# JLINK-OB.net
KiCad netlist of a schematic drawn in EasyEDA Pro
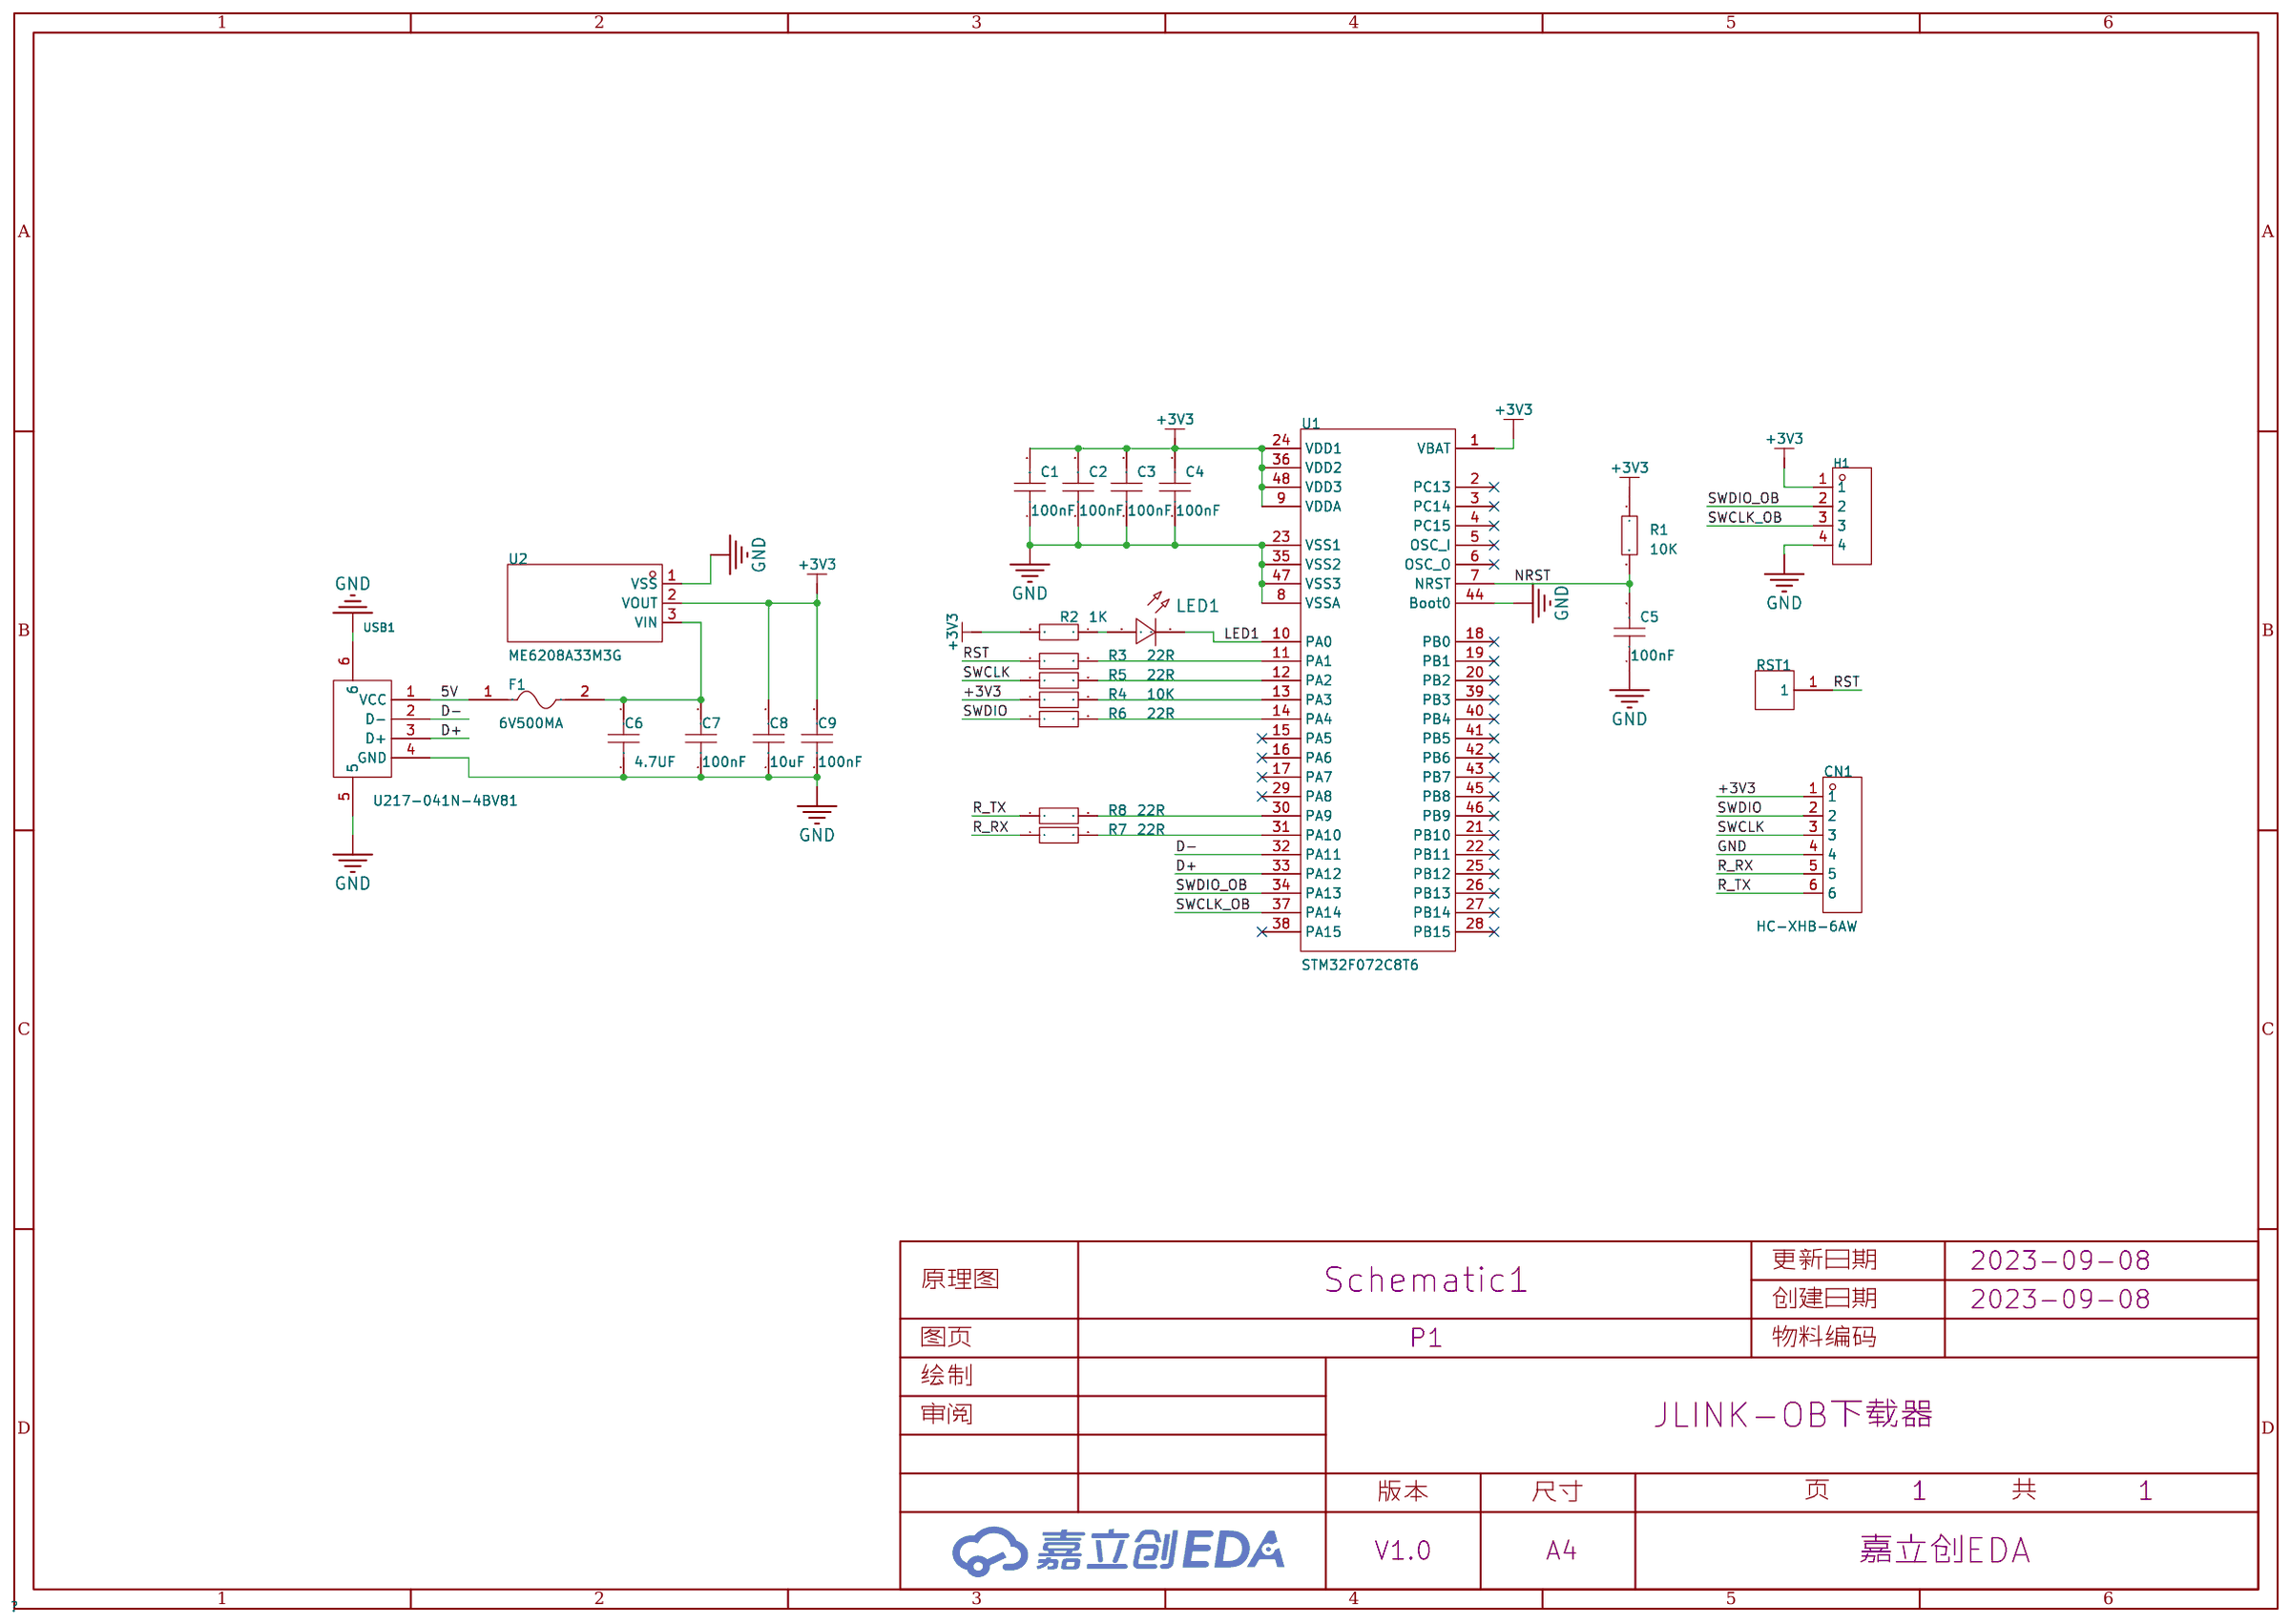
[diagram p0: schematic sheet]

(export (version "E")
  (design (tool "Eeschema 10.0.6"))
  (components
    (comp (ref "C1")
      (value "100nF")
      (footprint "easyedapro:C0603")
      (libsource (lib "easyedapro") (part "CapAcitance"))
    )
    (comp (ref "C2")
      (value "100nF")
      (footprint "easyedapro:C0603")
      (libsource (lib "easyedapro") (part "CapAcitance"))
    )
    (comp (ref "C3")
      (value "100nF")
      (footprint "easyedapro:C0603")
      (libsource (lib "easyedapro") (part "CapAcitance"))
    )
    (comp (ref "C4")
      (value "100nF")
      (footprint "easyedapro:C0603")
      (libsource (lib "easyedapro") (part "CapAcitance"))
    )
    (comp (ref "C5")
      (value "100nF")
      (footprint "easyedapro:C0603")
      (libsource (lib "easyedapro") (part "CapAcitance"))
    )
    (comp (ref "C6")
      (value "4.7UF")
      (footprint "easyedapro:C0603")
      (libsource (lib "easyedapro") (part "CapAcitance"))
    )
    (comp (ref "C7")
      (value "100nF")
      (footprint "easyedapro:C0603")
      (libsource (lib "easyedapro") (part "CapAcitance"))
    )
    (comp (ref "C8")
      (value "10uF")
      (footprint "easyedapro:C0603")
      (libsource (lib "easyedapro") (part "CapAcitance"))
    )
    (comp (ref "C9")
      (value "100nF")
      (footprint "easyedapro:C0603")
      (libsource (lib "easyedapro") (part "CapAcitance"))
    )
    (comp (ref "CN1")
      (value "HC-XHB-6AW")
      (footprint "easyedapro:CONN-TH_6P-P2.50_HCTL_HC-XHB-6AW")
      (description "参考系列:-;间距:2.5mm;插针结构:1x6P;排数:1;每排PIN数:6;行距:-;公母:公型插针;安装方式:弯插;额定电流:3A;工作温度范围:-25°C~+85°C;")
      (fields (field (name "Manufacturer") "HCTL(华灿天禄)"))
      (libsource (lib "easyedapro") (part "HC-XHB-6AW"))
    )
    (comp (ref "F1")
      (value "6V500MA")
      (footprint "easyedapro:F0805")
      (description "最大电压:24V;最大电流:100A;保持电流:100mA;跳闸电流:300mA;")
      (fields (field (name "Manufacturer") "台湾陆海"))
      (libsource (lib "easyedapro") (part "SMD0805-010-24V"))
    )
    (comp (ref "H1")
      (value "~")
      (footprint "easyedapro:HDR-TH_4P-P2.54-V-F")
      (libsource (lib "easyedapro") (part "2.54-1*4P母"))
    )
    (comp (ref "LED1")
      (value "~")
      (footprint "easyedapro:LED_0603")
      (libsource (lib "easyedapro") (part "LED_R"))
    )
    (comp (ref "R1") (value "10K") (footprint "easyedapro:R0603") (libsource (lib "easyedapro") (part "电阻")))
    (comp (ref "R2") (value "1K") (footprint "easyedapro:R0603") (libsource (lib "easyedapro") (part "电阻")))
    (comp (ref "R3") (value "22R") (footprint "easyedapro:R0603") (libsource (lib "easyedapro") (part "电阻")))
    (comp (ref "R4") (value "10K") (footprint "easyedapro:R0603") (libsource (lib "easyedapro") (part "电阻")))
    (comp (ref "R5") (value "22R") (footprint "easyedapro:R0603") (libsource (lib "easyedapro") (part "电阻")))
    (comp (ref "R6") (value "22R") (footprint "easyedapro:R0603") (libsource (lib "easyedapro") (part "电阻")))
    (comp (ref "R7") (value "22R") (footprint "easyedapro:R0603") (libsource (lib "easyedapro") (part "电阻")))
    (comp (ref "R8") (value "22R") (footprint "easyedapro:R0603") (libsource (lib "easyedapro") (part "电阻")))
    (comp (ref "RST1")
      (value "~")
      (footprint "easyedapro:PAD_1.5*1.5MM")
      (libsource (lib "easyedapro") (part "测试点1.5x1.5mm"))
    )
    (comp (ref "U1")
      (value "STM32F072C8T6")
      (footprint "easyedapro:LQFP-48_L7.0-W7.0-P0.50-LS9.0-BL")
      (fields (field (name "Manufacturer") "ST(意法半导体)"))
      (libsource (lib "easyedapro") (part "STM32F072C8T6"))
    )
    (comp (ref "U2")
      (value "ME6208A33M3G")
      (footprint "easyedapro:SOT-23-3_L2.9-W1.3-P1.90-LS2.4-BR")
      (description "输出类型:固定;输出极性:正;最大输入电压:18V;输出电压:3.3V;输出电流:200mA;电源纹波抑制比(PSRR):-;")
      (fields (field (name "Manufacturer") "MICRONE(南京微盟)"))
      (libsource (lib "easyedapro") (part "ME6208A33M3G"))
    )
    (comp (ref "USB1")
      (value "U217-041N-4BV81")
      (footprint "easyedapro:USB-A-SMD_U217-041N-4BV81")
      (fields (field (name "Manufacturer") "XKB Connectivity(中国星坤)"))
      (libsource (lib "easyedapro") (part "U217-04XN-XXR84"))
    )
  )
  (nets
    (net (code "1") (name "+3V3") (class "Default")
      (node (ref "C1") (pin "2") (pinfunction "2_2") (pintype "input"))
      (node (ref "C2") (pin "2") (pinfunction "2_2") (pintype "input"))
      (node (ref "C3") (pin "2") (pinfunction "2_2") (pintype "input"))
      (node (ref "C4") (pin "2") (pinfunction "2_2") (pintype "input"))
      (node (ref "C8") (pin "2") (pinfunction "2_2") (pintype "input"))
      (node (ref "C9") (pin "2") (pinfunction "2_2") (pintype "input"))
      (node (ref "CN1") (pin "1") (pinfunction "1_1") (pintype "input"))
      (node (ref "H1") (pin "1") (pinfunction "1_1") (pintype "input"))
      (node (ref "R1") (pin "1") (pinfunction "1_1") (pintype "input"))
      (node (ref "R2") (pin "2") (pinfunction "2_2") (pintype "input"))
      (node (ref "R4") (pin "1") (pinfunction "1_1") (pintype "input"))
      (node (ref "U1") (pin "1") (pinfunction "VBAT_1") (pintype "input"))
      (node (ref "U1") (pin "24") (pinfunction "VDD1_24") (pintype "input"))
      (node (ref "U1") (pin "36") (pinfunction "VDD2_36") (pintype "input"))
      (node (ref "U1") (pin "48") (pinfunction "VDD3_48") (pintype "input"))
      (node (ref "U1") (pin "9") (pinfunction "VDDA_9") (pintype "input"))
      (node (ref "U2") (pin "2") (pinfunction "VOUT_2") (pintype "input"))
    )
    (net (code "2") (name "/5V") (class "Default")
      (node (ref "F1") (pin "1") (pinfunction "1_1") (pintype "input"))
      (node (ref "USB1") (pin "1") (pinfunction "VCC_1") (pintype "input"))
    )
    (net (code "3") (name "/D+") (class "Default")
      (node (ref "U1") (pin "33") (pinfunction "PA12_33") (pintype "input"))
      (node (ref "USB1") (pin "3") (pinfunction "D+_3") (pintype "input"))
    )
    (net (code "4") (name "/D-") (class "Default")
      (node (ref "U1") (pin "32") (pinfunction "PA11_32") (pintype "input"))
      (node (ref "USB1") (pin "2") (pinfunction "D-_2") (pintype "input"))
    )
    (net (code "5") (name "/LED1") (class "Default")
      (node (ref "LED1") (pin "1") (pinfunction "C_1") (pintype "input"))
      (node (ref "U1") (pin "10") (pinfunction "PA0_10") (pintype "input"))
    )
    (net (code "6") (name "/NRST") (class "Default")
      (node (ref "C5") (pin "2") (pinfunction "2_2") (pintype "input"))
      (node (ref "R1") (pin "2") (pinfunction "2_2") (pintype "input"))
      (node (ref "U1") (pin "7") (pinfunction "NRST_7") (pintype "input"))
    )
    (net (code "7") (name "/RST") (class "Default")
      (node (ref "R3") (pin "1") (pinfunction "1_1") (pintype "input"))
      (node (ref "RST1") (pin "1") (pinfunction "1_1") (pintype "input"))
    )
    (net (code "8") (name "/R_RX") (class "Default")
      (node (ref "CN1") (pin "5") (pinfunction "5_5") (pintype "input"))
      (node (ref "R7") (pin "1") (pinfunction "1_1") (pintype "input"))
    )
    (net (code "9") (name "/R_TX") (class "Default")
      (node (ref "CN1") (pin "6") (pinfunction "6_6") (pintype "input"))
      (node (ref "R8") (pin "1") (pinfunction "1_1") (pintype "input"))
    )
    (net (code "10") (name "/SWCLK") (class "Default")
      (node (ref "CN1") (pin "3") (pinfunction "3_3") (pintype "input"))
      (node (ref "R5") (pin "1") (pinfunction "1_1") (pintype "input"))
    )
    (net (code "11") (name "/SWCLK_OB") (class "Default")
      (node (ref "H1") (pin "3") (pinfunction "3_3") (pintype "input"))
      (node (ref "U1") (pin "37") (pinfunction "PA14_37") (pintype "input"))
    )
    (net (code "12") (name "/SWDIO") (class "Default")
      (node (ref "CN1") (pin "2") (pinfunction "2_2") (pintype "input"))
      (node (ref "R6") (pin "1") (pinfunction "1_1") (pintype "input"))
    )
    (net (code "13") (name "/SWDIO_OB") (class "Default")
      (node (ref "H1") (pin "2") (pinfunction "2_2") (pintype "input"))
      (node (ref "U1") (pin "34") (pinfunction "PA13_34") (pintype "input"))
    )
    (net (code "14") (name "GND") (class "Default")
      (node (ref "C1") (pin "1") (pinfunction "1_1") (pintype "input"))
      (node (ref "C2") (pin "1") (pinfunction "1_1") (pintype "input"))
      (node (ref "C3") (pin "1") (pinfunction "1_1") (pintype "input"))
      (node (ref "C4") (pin "1") (pinfunction "1_1") (pintype "input"))
      (node (ref "C5") (pin "1") (pinfunction "1_1") (pintype "input"))
      (node (ref "C6") (pin "1") (pinfunction "1_1") (pintype "input"))
      (node (ref "C7") (pin "1") (pinfunction "1_1") (pintype "input"))
      (node (ref "C8") (pin "1") (pinfunction "1_1") (pintype "input"))
      (node (ref "C9") (pin "1") (pinfunction "1_1") (pintype "input"))
      (node (ref "CN1") (pin "4") (pinfunction "4_4") (pintype "input"))
      (node (ref "H1") (pin "4") (pinfunction "4_4") (pintype "input"))
      (node (ref "U1") (pin "23") (pinfunction "VSS1_23") (pintype "input"))
      (node (ref "U1") (pin "35") (pinfunction "VSS2_35") (pintype "input"))
      (node (ref "U1") (pin "44") (pinfunction "Boot0_44") (pintype "input"))
      (node (ref "U1") (pin "47") (pinfunction "VSS3_47") (pintype "input"))
      (node (ref "U1") (pin "8") (pinfunction "VSSA_8") (pintype "input"))
      (node (ref "U2") (pin "1") (pinfunction "VSS_1") (pintype "input"))
      (node (ref "USB1") (pin "4") (pinfunction "GND_4") (pintype "input"))
      (node (ref "USB1") (pin "5") (pinfunction "5_5") (pintype "input"))
      (node (ref "USB1") (pin "6") (pinfunction "6_6") (pintype "input"))
    )
    (net (code "15") (name "Net-(LED1-A)") (class "Default")
      (node (ref "LED1") (pin "2") (pinfunction "A_2") (pintype "input"))
      (node (ref "R2") (pin "1") (pinfunction "1_1") (pintype "input"))
    )
    (net (code "16") (name "Net-(U1-PA1)") (class "Default")
      (node (ref "R3") (pin "2") (pinfunction "2_2") (pintype "input"))
      (node (ref "U1") (pin "11") (pinfunction "PA1_11") (pintype "input"))
    )
    (net (code "17") (name "Net-(U1-PA2)") (class "Default")
      (node (ref "R5") (pin "2") (pinfunction "2_2") (pintype "input"))
      (node (ref "U1") (pin "12") (pinfunction "PA2_12") (pintype "input"))
    )
    (net (code "18") (name "Net-(U1-PA3)") (class "Default")
      (node (ref "R4") (pin "2") (pinfunction "2_2") (pintype "input"))
      (node (ref "U1") (pin "13") (pinfunction "PA3_13") (pintype "input"))
    )
    (net (code "19") (name "Net-(U1-PA4)") (class "Default")
      (node (ref "R6") (pin "2") (pinfunction "2_2") (pintype "input"))
      (node (ref "U1") (pin "14") (pinfunction "PA4_14") (pintype "input"))
    )
    (net (code "20") (name "Net-(U1-PA9)") (class "Default")
      (node (ref "R8") (pin "2") (pinfunction "2_2") (pintype "input"))
      (node (ref "U1") (pin "30") (pinfunction "PA9_30") (pintype "input"))
    )
    (net (code "21") (name "Net-(U1-PA10)") (class "Default")
      (node (ref "R7") (pin "2") (pinfunction "2_2") (pintype "input"))
      (node (ref "U1") (pin "31") (pinfunction "PA10_31") (pintype "input"))
    )
    (net (code "22") (name "Net-(U2-VIN)") (class "Default")
      (node (ref "C6") (pin "2") (pinfunction "2_2") (pintype "input"))
      (node (ref "C7") (pin "2") (pinfunction "2_2") (pintype "input"))
      (node (ref "F1") (pin "2") (pinfunction "2_2") (pintype "input"))
      (node (ref "U2") (pin "3") (pinfunction "VIN_3") (pintype "input"))
    )
    (net (code "23") (name "unconnected-(U1-OSC_I-Pad5)") (class "Default")
      (node (ref "U1") (pin "5") (pinfunction "OSC_I_5") (pintype "input+no_connect"))
    )
    (net (code "24") (name "unconnected-(U1-OSC_O-Pad6)") (class "Default")
      (node (ref "U1") (pin "6") (pinfunction "OSC_O_6") (pintype "input+no_connect"))
    )
    (net (code "25") (name "unconnected-(U1-PA5-Pad15)") (class "Default")
      (node (ref "U1") (pin "15") (pinfunction "PA5_15") (pintype "input+no_connect"))
    )
    (net (code "26") (name "unconnected-(U1-PA6-Pad16)") (class "Default")
      (node (ref "U1") (pin "16") (pinfunction "PA6_16") (pintype "input+no_connect"))
    )
    (net (code "27") (name "unconnected-(U1-PA7-Pad17)") (class "Default")
      (node (ref "U1") (pin "17") (pinfunction "PA7_17") (pintype "input+no_connect"))
    )
    (net (code "28") (name "unconnected-(U1-PA8-Pad29)") (class "Default")
      (node (ref "U1") (pin "29") (pinfunction "PA8_29") (pintype "input+no_connect"))
    )
    (net (code "29") (name "unconnected-(U1-PA15-Pad38)") (class "Default")
      (node (ref "U1") (pin "38") (pinfunction "PA15_38") (pintype "input+no_connect"))
    )
    (net (code "30") (name "unconnected-(U1-PB0-Pad18)") (class "Default")
      (node (ref "U1") (pin "18") (pinfunction "PB0_18") (pintype "input+no_connect"))
    )
    (net (code "31") (name "unconnected-(U1-PB1-Pad19)") (class "Default")
      (node (ref "U1") (pin "19") (pinfunction "PB1_19") (pintype "input+no_connect"))
    )
    (net (code "32") (name "unconnected-(U1-PB2-Pad20)") (class "Default")
      (node (ref "U1") (pin "20") (pinfunction "PB2_20") (pintype "input+no_connect"))
    )
    (net (code "33") (name "unconnected-(U1-PB3-Pad39)") (class "Default")
      (node (ref "U1") (pin "39") (pinfunction "PB3_39") (pintype "input+no_connect"))
    )
    (net (code "34") (name "unconnected-(U1-PB4-Pad40)") (class "Default")
      (node (ref "U1") (pin "40") (pinfunction "PB4_40") (pintype "input+no_connect"))
    )
    (net (code "35") (name "unconnected-(U1-PB5-Pad41)") (class "Default")
      (node (ref "U1") (pin "41") (pinfunction "PB5_41") (pintype "input+no_connect"))
    )
    (net (code "36") (name "unconnected-(U1-PB6-Pad42)") (class "Default")
      (node (ref "U1") (pin "42") (pinfunction "PB6_42") (pintype "input+no_connect"))
    )
    (net (code "37") (name "unconnected-(U1-PB7-Pad43)") (class "Default")
      (node (ref "U1") (pin "43") (pinfunction "PB7_43") (pintype "input+no_connect"))
    )
    (net (code "38") (name "unconnected-(U1-PB8-Pad45)") (class "Default")
      (node (ref "U1") (pin "45") (pinfunction "PB8_45") (pintype "input+no_connect"))
    )
    (net (code "39") (name "unconnected-(U1-PB9-Pad46)") (class "Default")
      (node (ref "U1") (pin "46") (pinfunction "PB9_46") (pintype "input+no_connect"))
    )
    (net (code "40") (name "unconnected-(U1-PB10-Pad21)") (class "Default")
      (node (ref "U1") (pin "21") (pinfunction "PB10_21") (pintype "input+no_connect"))
    )
    (net (code "41") (name "unconnected-(U1-PB11-Pad22)") (class "Default")
      (node (ref "U1") (pin "22") (pinfunction "PB11_22") (pintype "input+no_connect"))
    )
    (net (code "42") (name "unconnected-(U1-PB12-Pad25)") (class "Default")
      (node (ref "U1") (pin "25") (pinfunction "PB12_25") (pintype "input+no_connect"))
    )
    (net (code "43") (name "unconnected-(U1-PB13-Pad26)") (class "Default")
      (node (ref "U1") (pin "26") (pinfunction "PB13_26") (pintype "input+no_connect"))
    )
    (net (code "44") (name "unconnected-(U1-PB14-Pad27)") (class "Default")
      (node (ref "U1") (pin "27") (pinfunction "PB14_27") (pintype "input+no_connect"))
    )
    (net (code "45") (name "unconnected-(U1-PB15-Pad28)") (class "Default")
      (node (ref "U1") (pin "28") (pinfunction "PB15_28") (pintype "input+no_connect"))
    )
    (net (code "46") (name "unconnected-(U1-PC13-Pad2)") (class "Default")
      (node (ref "U1") (pin "2") (pinfunction "PC13_2") (pintype "input+no_connect"))
    )
    (net (code "47") (name "unconnected-(U1-PC14-Pad3)") (class "Default")
      (node (ref "U1") (pin "3") (pinfunction "PC14_3") (pintype "input+no_connect"))
    )
    (net (code "48") (name "unconnected-(U1-PC15-Pad4)") (class "Default")
      (node (ref "U1") (pin "4") (pinfunction "PC15_4") (pintype "input+no_connect"))
    )
  )
)
